# LDP_PWR_v2_0.net
KiCad netlist of a schematic drawn in Altium Designer
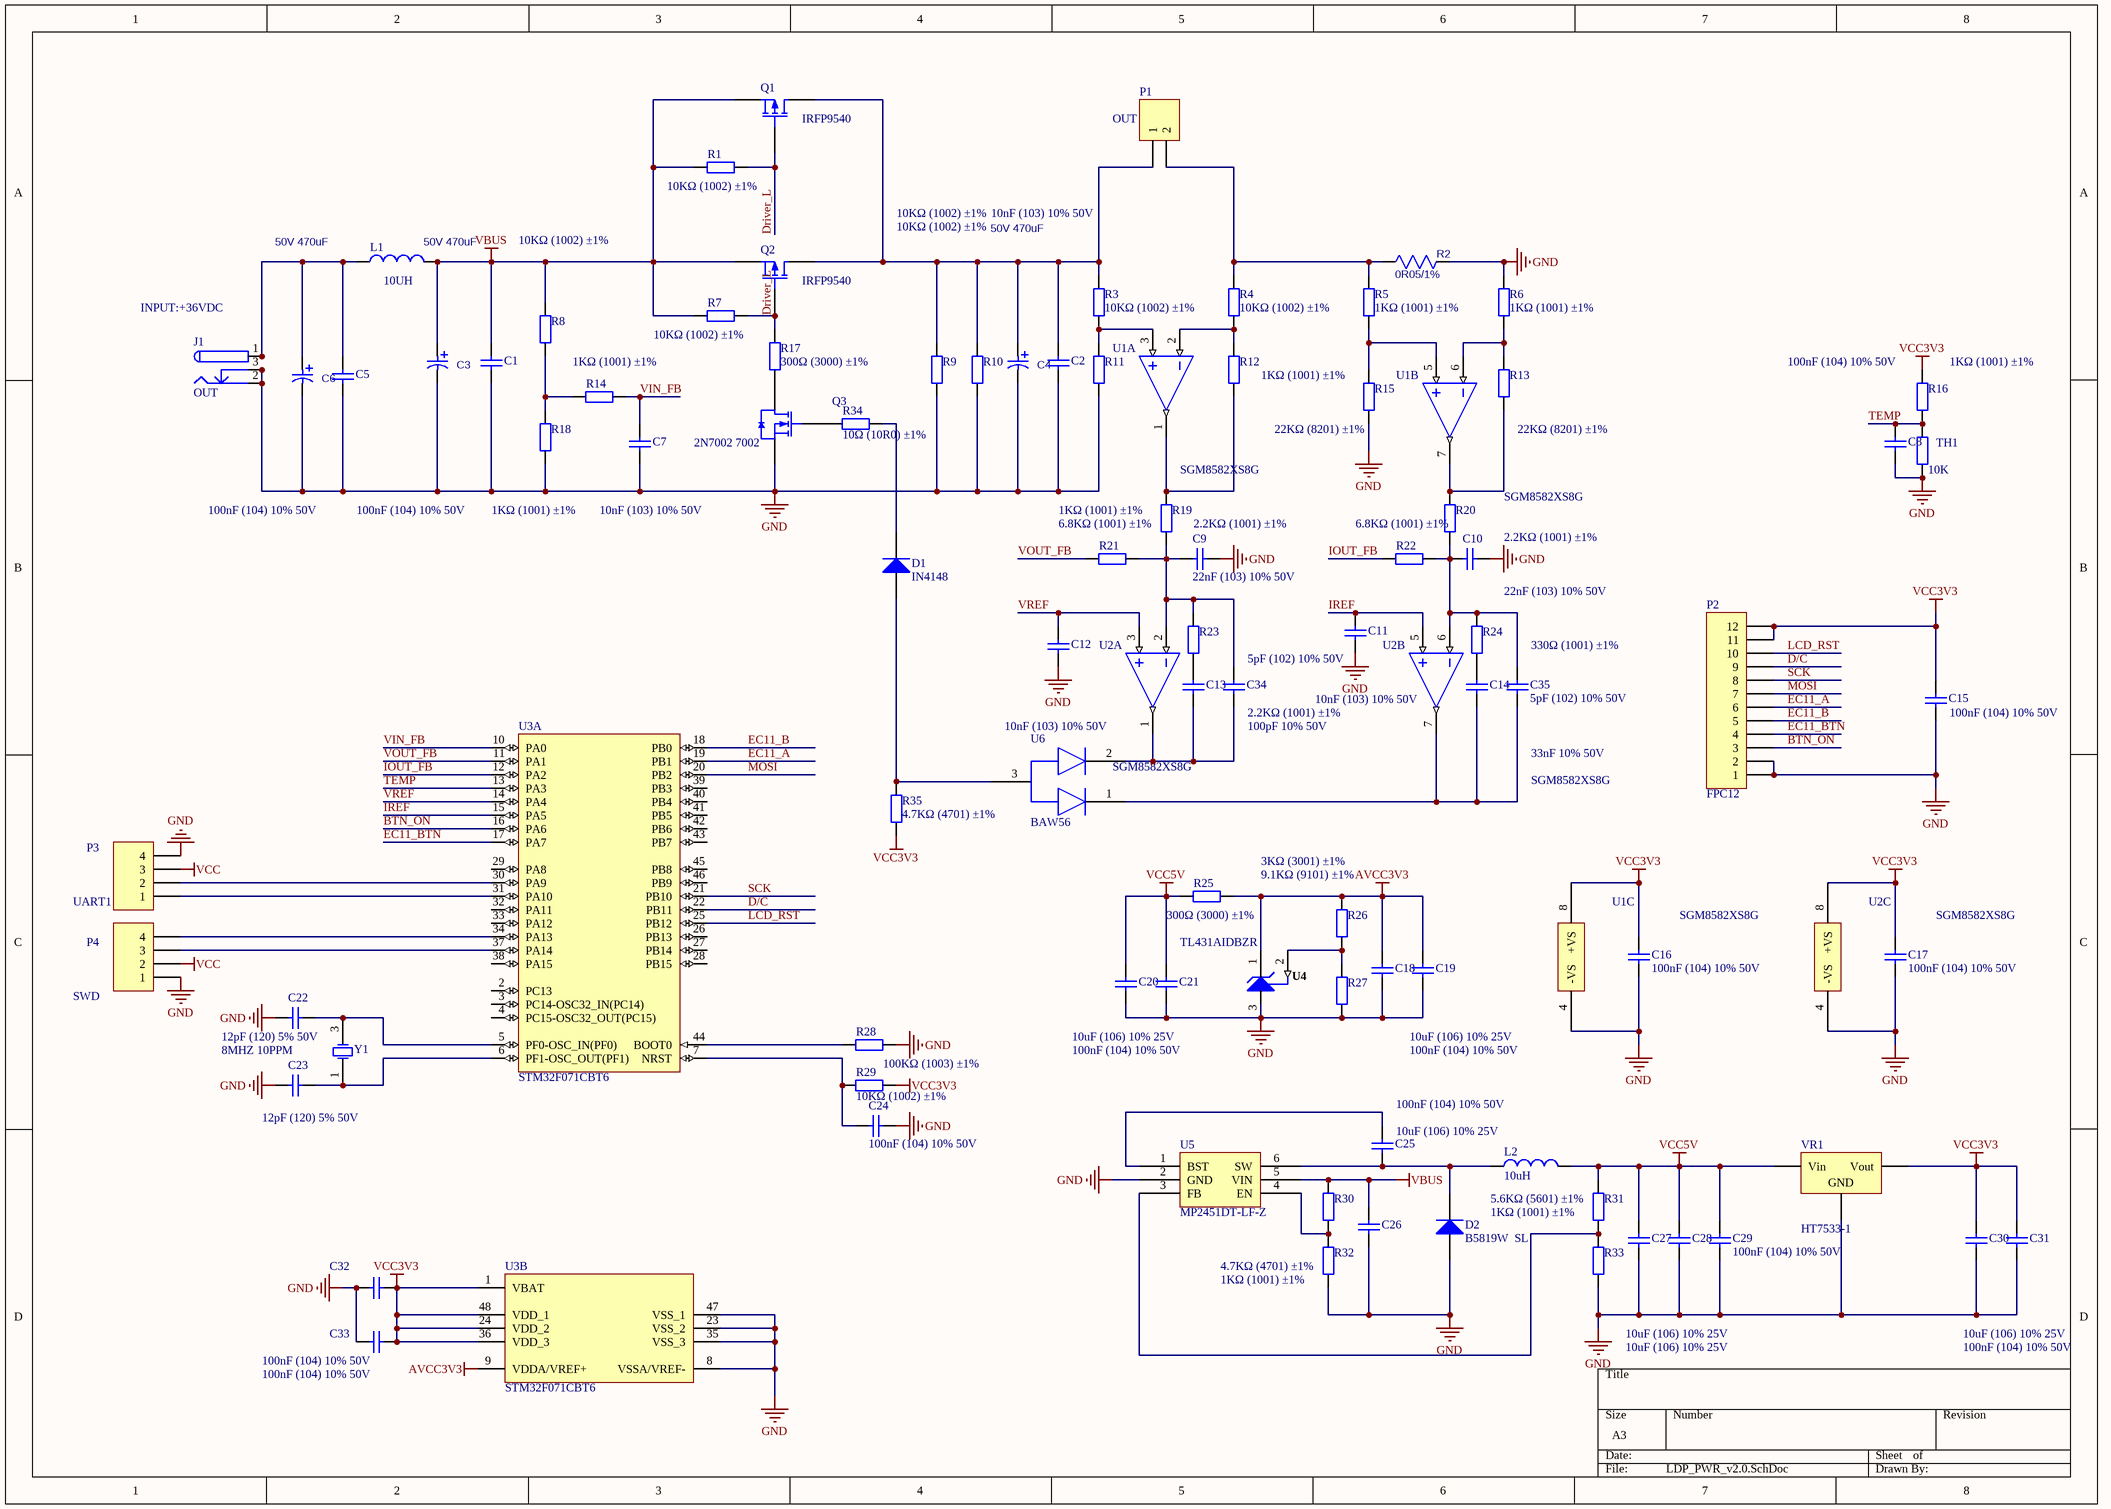
[diagram p0: LDP_PWR_v2.0.SchDoc]

(export (version "E")
  (design (tool "Eeschema 10.0.6"))
  (components
    (comp (ref "C1")
      (value "100nF (104) 10% 50V")
      (footprint "0603_C")
      (description "贴片电容")
      (libsource (lib "Cap") (part "0603 100nF (104) 10% 50V"))
    )
    (comp (ref "C2")
      (value "10nF (103) 10% 50V")
      (footprint "0603_C")
      (description "贴片电容")
      (libsource (lib "Cap") (part "0603 10nF (103) 10% 50V"))
    )
    (comp (ref "C3")
      (value "50V 470uF")
      (footprint "CAP/DIP/10-5")
      (description "Capacitor;400V;20%")
      (fields (field (name "MANUFACTURER") "{Manufacturer}") (field (name "PART NUMBER") "07.0686"))
      (libsource (lib "MPSLab") (part "CAP/ELECT/DIP/OD16.0P7.5"))
    )
    (comp (ref "C4")
      (value "50V 470uF")
      (footprint "CAP/DIP/10-5")
      (description "Capacitor;400V;20%")
      (fields (field (name "MANUFACTURER") "{Manufacturer}") (field (name "PART NUMBER") "07.0686"))
      (libsource (lib "MPSLab") (part "CAP/ELECT/DIP/OD16.0P7.5"))
    )
    (comp (ref "C5")
      (value "100nF (104) 10% 50V")
      (footprint "0603_C")
      (description "贴片电容")
      (libsource (lib "Cap") (part "0603 100nF (104) 10% 50V"))
    )
    (comp (ref "C6")
      (value "50V 470uF")
      (footprint "CAP/DIP/10-5")
      (description "Capacitor;400V;20%")
      (fields (field (name "MANUFACTURER") "{Manufacturer}") (field (name "PART NUMBER") "07.0686"))
      (libsource (lib "MPSLab") (part "CAP/ELECT/DIP/OD16.0P7.5"))
    )
    (comp (ref "C7")
      (value "10nF (103) 10% 50V")
      (footprint "0603_C")
      (description "贴片电容")
      (libsource (lib "Cap") (part "0603 10nF (103) 10% 50V"))
    )
    (comp (ref "C8")
      (value "100nF (104) 10% 50V")
      (footprint "0603_C")
      (description "贴片电容")
      (libsource (lib "Cap") (part "0603 100nF (104) 10% 50V"))
    )
    (comp (ref "C9")
      (value "22nF (103) 10% 50V")
      (footprint "0603_C")
      (description "贴片电容")
      (libsource (lib "Cap") (part "0603 10nF (103) 10% 50V"))
    )
    (comp (ref "C10")
      (value "22nF (103) 10% 50V")
      (footprint "0603_C")
      (description "贴片电容")
      (libsource (lib "Cap") (part "0603 10nF (103) 10% 50V"))
    )
    (comp (ref "C11")
      (value "10nF (103) 10% 50V")
      (footprint "0603_C")
      (description "贴片电容")
      (libsource (lib "Cap") (part "0603 10nF (103) 10% 50V"))
    )
    (comp (ref "C12")
      (value "10nF (103) 10% 50V")
      (footprint "0603_C")
      (description "贴片电容")
      (libsource (lib "Cap") (part "0603 10nF (103) 10% 50V"))
    )
    (comp (ref "C13")
      (value "100pF 10% 50V")
      (footprint "0603_C")
      (description "贴片电容")
      (libsource (lib "Cap") (part "0603 10nF (103) 10% 50V"))
    )
    (comp (ref "C14")
      (value "33nF 10% 50V")
      (footprint "0603_C")
      (description "贴片电容")
      (libsource (lib "Cap") (part "0603 10nF (103) 10% 50V"))
    )
    (comp (ref "C15")
      (value "100nF (104) 10% 50V")
      (footprint "0603_C")
      (description "贴片电容")
      (libsource (lib "Cap") (part "0603 100nF (104) 10% 50V"))
    )
    (comp (ref "C16")
      (value "100nF (104) 10% 50V")
      (footprint "0603_C")
      (description "贴片电容")
      (libsource (lib "Cap") (part "0603 100nF (104) 10% 50V"))
    )
    (comp (ref "C17")
      (value "100nF (104) 10% 50V")
      (footprint "0603_C")
      (description "贴片电容")
      (libsource (lib "Cap") (part "0603 100nF (104) 10% 50V"))
    )
    (comp (ref "C18")
      (value "10uF (106) 10% 25V")
      (footprint "0805_C")
      (description "贴片电容")
      (libsource (lib "Cap") (part "0805 10uF (106) 10% 25V"))
    )
    (comp (ref "C19")
      (value "100nF (104) 10% 50V")
      (footprint "0603_C")
      (description "贴片电容")
      (libsource (lib "Cap") (part "0603 100nF (104) 10% 50V"))
    )
    (comp (ref "C20")
      (value "10uF (106) 10% 25V")
      (footprint "0805_C")
      (description "贴片电容")
      (libsource (lib "Cap") (part "0805 10uF (106) 10% 25V"))
    )
    (comp (ref "C21")
      (value "100nF (104) 10% 50V")
      (footprint "0603_C")
      (description "贴片电容")
      (libsource (lib "Cap") (part "0603 100nF (104) 10% 50V"))
    )
    (comp (ref "C22")
      (value "12pF (120) 5% 50V")
      (footprint "0603_C")
      (description "贴片电容")
      (libsource (lib "Cap") (part "0603 12pF (120) 5% 50V"))
    )
    (comp (ref "C23")
      (value "12pF (120) 5% 50V")
      (footprint "0603_C")
      (description "贴片电容")
      (libsource (lib "Cap") (part "0603 12pF (120) 5% 50V"))
    )
    (comp (ref "C24")
      (value "100nF (104) 10% 50V")
      (footprint "0603_C")
      (description "贴片电容")
      (libsource (lib "Cap") (part "0603 100nF (104) 10% 50V"))
    )
    (comp (ref "C25")
      (value "100nF (104) 10% 50V")
      (footprint "0603_C")
      (description "贴片电容")
      (libsource (lib "Cap") (part "0603 100nF (104) 10% 50V"))
    )
    (comp (ref "C26")
      (value "10uF (106) 10% 25V")
      (footprint "0805_C")
      (description "贴片电容")
      (libsource (lib "Cap") (part "0805 10uF (106) 10% 25V"))
    )
    (comp (ref "C27")
      (value "10uF (106) 10% 25V")
      (footprint "0805_C")
      (description "贴片电容")
      (libsource (lib "Cap") (part "0805 10uF (106) 10% 25V"))
    )
    (comp (ref "C28")
      (value "10uF (106) 10% 25V")
      (footprint "0805_C")
      (description "贴片电容")
      (libsource (lib "Cap") (part "0805 10uF (106) 10% 25V"))
    )
    (comp (ref "C29")
      (value "100nF (104) 10% 50V")
      (footprint "0603_C")
      (description "贴片电容")
      (libsource (lib "Cap") (part "0603 100nF (104) 10% 50V"))
    )
    (comp (ref "C30")
      (value "10uF (106) 10% 25V")
      (footprint "0805_C")
      (description "贴片电容")
      (libsource (lib "Cap") (part "0805 10uF (106) 10% 25V"))
    )
    (comp (ref "C31")
      (value "100nF (104) 10% 50V")
      (footprint "0603_C")
      (description "贴片电容")
      (libsource (lib "Cap") (part "0603 100nF (104) 10% 50V"))
    )
    (comp (ref "C32")
      (value "100nF (104) 10% 50V")
      (footprint "0603_C")
      (description "贴片电容")
      (libsource (lib "Cap") (part "0603 100nF (104) 10% 50V"))
    )
    (comp (ref "C33")
      (value "100nF (104) 10% 50V")
      (footprint "0603_C")
      (description "贴片电容")
      (libsource (lib "Cap") (part "0603 100nF (104) 10% 50V"))
    )
    (comp (ref "C34")
      (value "5pF (102) 10% 50V")
      (footprint "0603_C")
      (description "贴片电容")
      (libsource (lib "Cap") (part "0603 1nF (102) 10% 50V"))
    )
    (comp (ref "C35")
      (value "5pF (102) 10% 50V")
      (footprint "0603_C")
      (description "贴片电容")
      (libsource (lib "Cap") (part "0603 1nF (102) 10% 50V"))
    )
    (comp (ref "D1")
      (value "IN4148")
      (footprint "SOD-123")
      (description "Default Diode")
      (fields (field (name "PUBLISHER") "Altium Limited"))
      (libsource (lib "Miscellaneous Devices") (part "Diode"))
    )
    (comp (ref "D2")
      (value "B5819W  SL")
      (footprint "SOD-123")
      (description "肖特基二极管")
      (libsource (lib "Diode") (part "SOD-123 B5819W  SL"))
    )
    (comp (ref "J1")
      (value "OUT")
      (footprint "CH3.96")
      (description "Low Voltage Power Supply Connector")
      (fields (field (name "PUBLISHER") "Altium Limited"))
      (libsource (lib "Miscellaneous Connectors") (part "PWR2.5"))
    )
    (comp (ref "L1")
      (value "10UH")
      (footprint "L/DIP_6X25")
      (description "Inductor")
      (fields (field (name "PUBLISHER") "Altium Limited"))
      (libsource (lib "Miscellaneous Devices") (part "Inductor"))
    )
    (comp (ref "L2")
      (value "10uH")
      (footprint "CD43 - duplicate")
      (description "Inductor")
      (fields (field (name "PUBLISHER") "Altium Limited"))
      (libsource (lib "Miscellaneous Devices") (part "Inductor"))
    )
    (comp (ref "P1")
      (value "OUT")
      (footprint "CH3.96")
      (description "Header, 2-Pin")
      (fields (field (name "PUBLISHER") "Altium Limited"))
      (libsource (lib "Miscellaneous Connectors") (part "Header 2"))
    )
    (comp (ref "P2")
      (value "FPC12")
      (footprint "FPC_12")
      (description "Header, 12-Pin")
      (fields (field (name "PUBLISHER") "Altium Limited"))
      (libsource (lib "Miscellaneous Connectors") (part "Header 12"))
    )
    (comp (ref "P3")
      (value "UART1")
      (footprint "HDR1X4")
      (description "Header, 4-Pin")
      (fields (field (name "PUBLISHER") "Altium Limited"))
      (libsource (lib "Miscellaneous Connectors") (part "Header 4"))
    )
    (comp (ref "P4")
      (value "SWD")
      (footprint "HDR1X4")
      (description "Header, 4-Pin")
      (fields (field (name "PUBLISHER") "Altium Limited"))
      (libsource (lib "Miscellaneous Connectors") (part "Header 4"))
    )
    (comp (ref "Q1")
      (value "IRFP9540")
      (footprint "TO-220(TO-220-3)")
      (description "P-Channel MOSFET")
      (fields (field (name "PUBLISHER") "Altium Limited"))
      (libsource (lib "Miscellaneous Devices") (part "MOSFET-P"))
    )
    (comp (ref "Q2")
      (value "IRFP9540")
      (footprint "TO-220(TO-220-3)")
      (description "P-Channel MOSFET")
      (fields (field (name "PUBLISHER") "Altium Limited"))
      (libsource (lib "Miscellaneous Devices") (part "MOSFET-P"))
    )
    (comp (ref "Q3")
      (value "2N7002 7002")
      (footprint "SOT-23(SOT-23-3)")
      (description "MOS(场效应管)")
      (libsource (lib "MOS") (part "2N7002 7002"))
    )
    (comp (ref "R1")
      (value "10KΩ (1002) ±1%")
      (footprint "1206_R")
      (description "贴片电阻")
      (libsource (lib "") (part "1206 10KΩ (1002) 1%_1"))
    )
    (comp (ref "R2")
      (value "0R05/1%")
      (footprint "2512_R")
      (description "Film Resistor;5%;")
      (fields (field (name "MANUFACTURER") "Yageo") (field (name "PART NUMBER") "06.0281"))
      (libsource (lib "MPSLab") (part "RES/0603"))
    )
    (comp (ref "R3")
      (value "10KΩ (1002) ±1%")
      (footprint "0603_R")
      (description "贴片电阻")
      (libsource (lib "") (part "0603 10KΩ (1002) 1%_1"))
    )
    (comp (ref "R4")
      (value "10KΩ (1002) ±1%")
      (footprint "0603_R")
      (description "贴片电阻")
      (libsource (lib "") (part "0603 10KΩ (1002) 1%_1"))
    )
    (comp (ref "R5")
      (value "1KΩ (1001) ±1%")
      (footprint "0603_R")
      (description "贴片电阻")
      (libsource (lib "") (part "0603 1KΩ (1001) 1%_1"))
    )
    (comp (ref "R6")
      (value "1KΩ (1001) ±1%")
      (footprint "0603_R")
      (description "贴片电阻")
      (libsource (lib "") (part "0603 1KΩ (1001) 1%_1"))
    )
    (comp (ref "R7")
      (value "10KΩ (1002) ±1%")
      (footprint "1206_R")
      (description "贴片电阻")
      (libsource (lib "") (part "1206 10KΩ (1002) 1%_1"))
    )
    (comp (ref "R8")
      (value "10KΩ (1002) ±1%")
      (footprint "0603_R")
      (description "贴片电阻")
      (libsource (lib "") (part "0603 10KΩ (1002) 1%_1"))
    )
    (comp (ref "R9")
      (value "10KΩ (1002) ±1%")
      (footprint "1206_R")
      (description "贴片电阻")
      (libsource (lib "RES") (part "1206 10KΩ (1002) 1%"))
    )
    (comp (ref "R10")
      (value "10KΩ (1002) ±1%")
      (footprint "1206_R")
      (description "贴片电阻")
      (libsource (lib "RES") (part "1206 10KΩ (1002) 1%"))
    )
    (comp (ref "R11")
      (value "1KΩ (1001) ±1%")
      (footprint "0603_R")
      (description "贴片电阻")
      (libsource (lib "") (part "0603 1KΩ (1001) 1%_1"))
    )
    (comp (ref "R12")
      (value "1KΩ (1001) ±1%")
      (footprint "0603_R")
      (description "贴片电阻")
      (libsource (lib "") (part "0603 1KΩ (1001) 1%_1"))
    )
    (comp (ref "R13")
      (value "22KΩ (8201) ±1%")
      (footprint "0603_R")
      (description "贴片电阻")
      (libsource (lib "RES") (part "0603 8.2KΩ (8201) 1%"))
    )
    (comp (ref "R14")
      (value "1KΩ (1001) ±1%")
      (footprint "0603_R")
      (description "贴片电阻")
      (libsource (lib "RES") (part "0603 1KΩ (1001) 1%"))
    )
    (comp (ref "R15")
      (value "22KΩ (8201) ±1%")
      (footprint "0603_R")
      (description "贴片电阻")
      (libsource (lib "RES") (part "0603 8.2KΩ (8201) 1%"))
    )
    (comp (ref "R16")
      (value "1KΩ (1001) ±1%")
      (footprint "0603_R")
      (description "贴片电阻")
      (libsource (lib "") (part "0603 1KΩ (1001) 1%_1"))
    )
    (comp (ref "R17")
      (value "300Ω (3000) ±1%")
      (footprint "1206_R")
      (description "贴片电阻")
      (libsource (lib "RES") (part "1206 300Ω (3000) 1%"))
    )
    (comp (ref "R18")
      (value "1KΩ (1001) ±1%")
      (footprint "0603_R")
      (description "贴片电阻")
      (libsource (lib "") (part "0603 1KΩ (1001) 1%_1"))
    )
    (comp (ref "R19")
      (value "2.2KΩ (1001) ±1%")
      (footprint "0603_R")
      (description "贴片电阻")
      (libsource (lib "") (part "0603 1KΩ (1001) 1%_1"))
    )
    (comp (ref "R20")
      (value "2.2KΩ (1001) ±1%")
      (footprint "0603_R")
      (description "贴片电阻")
      (libsource (lib "") (part "0603 1KΩ (1001) 1%_1"))
    )
    (comp (ref "R21")
      (value "6.8KΩ (1001) ±1%")
      (footprint "0603_R")
      (description "贴片电阻")
      (libsource (lib "RES") (part "0603 1KΩ (1001) 1%"))
    )
    (comp (ref "R22")
      (value "6.8KΩ (1001) ±1%")
      (footprint "0603_R")
      (description "贴片电阻")
      (libsource (lib "RES") (part "0603 1KΩ (1001) 1%"))
    )
    (comp (ref "R23")
      (value "2.2KΩ (1001) ±1%")
      (footprint "0603_R")
      (description "贴片电阻")
      (libsource (lib "") (part "0603 1KΩ (1001) 1%_2"))
    )
    (comp (ref "R24")
      (value "330Ω (1001) ±1%")
      (footprint "0603_R")
      (description "贴片电阻")
      (libsource (lib "") (part "0603 1KΩ (1001) 1%_2"))
    )
    (comp (ref "R25")
      (value "300Ω (3000) ±1%")
      (footprint "1206_R")
      (description "贴片电阻")
      (libsource (lib "") (part "1206 300Ω (3000) 1%_1"))
    )
    (comp (ref "R26")
      (value "3KΩ (3001) ±1%")
      (footprint "0603_R")
      (description "贴片电阻")
      (libsource (lib "RES") (part "0603 3KΩ (3001) 1%"))
    )
    (comp (ref "R27")
      (value "9.1KΩ (9101) ±1%")
      (footprint "0603_R")
      (description "贴片电阻")
      (libsource (lib "RES") (part "0603 9.1KΩ (9101) 1%"))
    )
    (comp (ref "R28")
      (value "100KΩ (1003) ±1%")
      (footprint "0603_R")
      (description "贴片电阻")
      (libsource (lib "RES") (part "0603 100KΩ (1003) 1%"))
    )
    (comp (ref "R29")
      (value "10KΩ (1002) ±1%")
      (footprint "0603_R")
      (description "贴片电阻")
      (libsource (lib "RES") (part "0603 10KΩ (1002) 1%"))
    )
    (comp (ref "R30")
      (value "4.7KΩ (4701) ±1%")
      (footprint "0603_R")
      (description "贴片电阻")
      (libsource (lib "RES") (part "0603 4.7KΩ (4701) 1%"))
    )
    (comp (ref "R31")
      (value "5.6KΩ (5601) ±1%")
      (footprint "0603_R")
      (description "贴片电阻")
      (libsource (lib "RES") (part "0603 5.6KΩ (5601) 1%"))
    )
    (comp (ref "R32")
      (value "1KΩ (1001) ±1%")
      (footprint "0603_R")
      (description "贴片电阻")
      (libsource (lib "") (part "0603 1KΩ (1001) 1%_1"))
    )
    (comp (ref "R33")
      (value "1KΩ (1001) ±1%")
      (footprint "0603_R")
      (description "贴片电阻")
      (libsource (lib "") (part "0603 1KΩ (1001) 1%_1"))
    )
    (comp (ref "R34")
      (value "10Ω (10R0) ±1%")
      (footprint "0603_R")
      (description "贴片电阻")
      (libsource (lib "RES") (part "0603 10Ω (10R0) 1%"))
    )
    (comp (ref "R35")
      (value "4.7KΩ (4701) ±1%")
      (footprint "0603_R")
      (description "贴片电阻")
      (libsource (lib "RES") (part "0603 4.7KΩ (4701) 1%"))
    )
    (comp (ref "TH1")
      (value "10K")
      (footprint "NTC_2.5MM")
      (description "Resistor")
      (fields (field (name "Comment") "NTC 10K") (field (name "PUBLISHER") "Altium Limited"))
      (libsource (lib "Miscellaneous Devices") (part "Res2"))
    )
    (comp (ref "U1")
      (value "SGM8582XS8G")
      (footprint "SOIC-8_208mil")
      (description "运放")
      (libsource (lib "") (part "SGM8292XS8G_1"))
    )
    (comp (ref "U2")
      (value "SGM8582XS8G")
      (footprint "SOIC-8_208mil")
      (description "运放")
      (libsource (lib "") (part "SGM8292XS8G_1"))
    )
    (comp (ref "U3")
      (value "STM32F071CBT6")
      (footprint "STM-LQFP48_N")
      (fields (field (name "PARTNUMBER") "STM32F303CCT6"))
      (libsource (lib "STMicroelectronics STM32 F3") (part "STM32F303CCT6"))
    )
    (comp (ref "U4")
      (value "TL431AIDBZR")
      (footprint "TI-DBZ3_N")
      (fields (field (name "MANUFACTURER") "Texas Instruments"))
      (libsource (lib "TI Power Management Shunt Voltage Reference") (part "TL431AIDBZR"))
    )
    (comp (ref "U5")
      (value "MP2451DT-LF-Z")
      (footprint "SOT-23-6")
      (description "DC-DC芯片")
      (libsource (lib "IC") (part "MP2451DT-LF-Z_[C14123]"))
    )
    (comp (ref "U6") (value "BAW56") (footprint "SOT-23(SOT-23-3)") (libsource (lib "Diode") (part "BAW56")))
    (comp (ref "VR1")
      (value "HT7533-1")
      (footprint "SOT-89(SOT-89-3)")
      (description "低压差线性稳压(LDO)")
      (libsource (lib "LDO") (part "SOT-89 HT7533-1"))
    )
    (comp (ref "Y1")
      (value "8MHZ 10PPM")
      (footprint "SMD-3225_4P")
      (description "贴片晶振")
      (libsource (lib "CrystalOscillator") (part "SMD-3225_4P  12MHZ 20PF 10PPM"))
    )
  )
  (nets
    (net (code "1") (name "/BTN_ON") (class "Default")
      (node (ref "P2") (pin "3") (pinfunction "3_3") (pintype "passive"))
      (node (ref "U3") (pin "16") (pinfunction "PA6_16") (pintype "bidirectional"))
    )
    (net (code "2") (name "/Driver_L") (class "Default")
      (node (ref "Q1") (pin "2") (pinfunction "G_2") (pintype "passive"))
      (node (ref "Q2") (pin "2") (pinfunction "G_2") (pintype "passive"))
      (node (ref "R1") (pin "2") (pinfunction "2_2") (pintype "passive"))
      (node (ref "R17") (pin "2") (pinfunction "2_2") (pintype "passive"))
      (node (ref "R7") (pin "2") (pinfunction "2_2") (pintype "passive"))
    )
    (net (code "3") (name "/D{slash}C") (class "Default")
      (node (ref "P2") (pin "9") (pinfunction "9_9") (pintype "passive"))
      (node (ref "U3") (pin "22") (pinfunction "PB11_22") (pintype "bidirectional"))
    )
    (net (code "4") (name "/EC11_A") (class "Default")
      (node (ref "P2") (pin "6") (pinfunction "6_6") (pintype "passive"))
      (node (ref "U3") (pin "19") (pinfunction "PB1_19") (pintype "bidirectional"))
    )
    (net (code "5") (name "/EC11_B") (class "Default")
      (node (ref "P2") (pin "5") (pinfunction "5_5") (pintype "passive"))
      (node (ref "U3") (pin "18") (pinfunction "PB0_18") (pintype "bidirectional"))
    )
    (net (code "6") (name "/EC11_BTN") (class "Default")
      (node (ref "P2") (pin "4") (pinfunction "4_4") (pintype "passive"))
      (node (ref "U3") (pin "17") (pinfunction "PA7_17") (pintype "bidirectional"))
    )
    (net (code "7") (name "/IOUT_FB") (class "Default")
      (node (ref "R22") (pin "2") (pinfunction "2_2") (pintype "passive"))
      (node (ref "U3") (pin "12") (pinfunction "PA2_12") (pintype "bidirectional"))
    )
    (net (code "8") (name "/IREF") (class "Default")
      (node (ref "C11") (pin "1") (pinfunction "1_1") (pintype "passive"))
      (node (ref "U2") (pin "5") (pinfunction "IN+_5") (pintype "input"))
      (node (ref "U3") (pin "15") (pinfunction "PA5_15") (pintype "bidirectional"))
    )
    (net (code "9") (name "/LCD_RST") (class "Default")
      (node (ref "P2") (pin "10") (pinfunction "10_10") (pintype "passive"))
      (node (ref "U3") (pin "25") (pinfunction "PB12_25") (pintype "bidirectional"))
    )
    (net (code "10") (name "/MOSI") (class "Default")
      (node (ref "P2") (pin "7") (pinfunction "7_7") (pintype "passive"))
      (node (ref "U3") (pin "20") (pinfunction "PB2_20") (pintype "bidirectional"))
    )
    (net (code "11") (name "/SCK") (class "Default")
      (node (ref "P2") (pin "8") (pinfunction "8_8") (pintype "passive"))
      (node (ref "U3") (pin "21") (pinfunction "PB10_21") (pintype "bidirectional"))
    )
    (net (code "12") (name "/TEMP") (class "Default")
      (node (ref "C8") (pin "2") (pinfunction "2_2") (pintype "passive"))
      (node (ref "R16") (pin "1") (pinfunction "1_1") (pintype "passive"))
      (node (ref "TH1") (pin "2") (pinfunction "2_2") (pintype "passive"))
      (node (ref "U3") (pin "13") (pinfunction "PA3_13") (pintype "bidirectional"))
    )
    (net (code "13") (name "/VIN_FB") (class "Default")
      (node (ref "C7") (pin "2") (pinfunction "2_2") (pintype "passive"))
      (node (ref "R14") (pin "1") (pinfunction "1_1") (pintype "passive"))
      (node (ref "U3") (pin "10") (pinfunction "PA0_10") (pintype "bidirectional"))
    )
    (net (code "14") (name "/VOUT_FB") (class "Default")
      (node (ref "R21") (pin "2") (pinfunction "2_2") (pintype "passive"))
      (node (ref "U3") (pin "11") (pinfunction "PA1_11") (pintype "bidirectional"))
    )
    (net (code "15") (name "/VREF") (class "Default")
      (node (ref "C12") (pin "1") (pinfunction "1_1") (pintype "passive"))
      (node (ref "U2") (pin "3") (pinfunction "IN+_3") (pintype "input"))
      (node (ref "U3") (pin "14") (pinfunction "PA4_14") (pintype "bidirectional"))
    )
    (net (code "16") (name "AVCC3V3") (class "Default")
      (node (ref "C18") (pin "2") (pinfunction "2_2") (pintype "passive"))
      (node (ref "C19") (pin "2") (pinfunction "2_2") (pintype "passive"))
      (node (ref "R25") (pin "2") (pinfunction "2_2") (pintype "passive"))
      (node (ref "R26") (pin "2") (pinfunction "2_2") (pintype "passive"))
      (node (ref "U3") (pin "9") (pinfunction "VDDA/VREF+_9") (pintype "power_in"))
      (node (ref "U4") (pin "1") (pinfunction "CATHODE_1") (pintype "passive"))
    )
    (net (code "17") (name "GND") (class "Default")
      (node (ref "C1") (pin "1") (pinfunction "1_1") (pintype "passive"))
      (node (ref "C10") (pin "1") (pinfunction "1_1") (pintype "passive"))
      (node (ref "C11") (pin "2") (pinfunction "2_2") (pintype "passive"))
      (node (ref "C12") (pin "2") (pinfunction "2_2") (pintype "passive"))
      (node (ref "C15") (pin "1") (pinfunction "1_1") (pintype "passive"))
      (node (ref "C16") (pin "1") (pinfunction "1_1") (pintype "passive"))
      (node (ref "C17") (pin "1") (pinfunction "1_1") (pintype "passive"))
      (node (ref "C18") (pin "1") (pinfunction "1_1") (pintype "passive"))
      (node (ref "C19") (pin "1") (pinfunction "1_1") (pintype "passive"))
      (node (ref "C2") (pin "2") (pinfunction "2_2") (pintype "passive"))
      (node (ref "C20") (pin "1") (pinfunction "1_1") (pintype "passive"))
      (node (ref "C21") (pin "1") (pinfunction "1_1") (pintype "passive"))
      (node (ref "C22") (pin "1") (pinfunction "1_1") (pintype "passive"))
      (node (ref "C23") (pin "1") (pinfunction "1_1") (pintype "passive"))
      (node (ref "C24") (pin "2") (pinfunction "2_2") (pintype "passive"))
      (node (ref "C26") (pin "1") (pinfunction "1_1") (pintype "passive"))
      (node (ref "C27") (pin "1") (pinfunction "1_1") (pintype "passive"))
      (node (ref "C28") (pin "1") (pinfunction "1_1") (pintype "passive"))
      (node (ref "C29") (pin "1") (pinfunction "1_1") (pintype "passive"))
      (node (ref "C3") (pin "2") (pintype "passive"))
      (node (ref "C30") (pin "1") (pinfunction "1_1") (pintype "passive"))
      (node (ref "C31") (pin "1") (pinfunction "1_1") (pintype "passive"))
      (node (ref "C32") (pin "2") (pinfunction "2_2") (pintype "passive"))
      (node (ref "C33") (pin "2") (pinfunction "2_2") (pintype "passive"))
      (node (ref "C4") (pin "2") (pintype "passive"))
      (node (ref "C5") (pin "1") (pinfunction "1_1") (pintype "passive"))
      (node (ref "C6") (pin "2") (pintype "passive"))
      (node (ref "C7") (pin "1") (pinfunction "1_1") (pintype "passive"))
      (node (ref "C8") (pin "1") (pinfunction "1_1") (pintype "passive"))
      (node (ref "C9") (pin "1") (pinfunction "1_1") (pintype "passive"))
      (node (ref "D2") (pin "1") (pinfunction "A_1") (pintype "passive"))
      (node (ref "J1") (pin "2") (pinfunction "2_2") (pintype "power_in"))
      (node (ref "J1") (pin "2A") (pinfunction "2A_2A") (pintype "power_in"))
      (node (ref "J1") (pin "2B") (pinfunction "2B_2B") (pintype "power_in"))
      (node (ref "J1") (pin "3") (pinfunction "3_3") (pintype "power_in"))
      (node (ref "J1") (pin "3A") (pinfunction "3A_3A") (pintype "power_in"))
      (node (ref "J1") (pin "3B") (pinfunction "3B_3B") (pintype "power_in"))
      (node (ref "P2") (pin "1") (pinfunction "1_1") (pintype "passive"))
      (node (ref "P2") (pin "2") (pinfunction "2_2") (pintype "passive"))
      (node (ref "P3") (pin "4") (pinfunction "4_4") (pintype "passive"))
      (node (ref "P4") (pin "1") (pinfunction "1_1") (pintype "passive"))
      (node (ref "Q3") (pin "2") (pinfunction "S_2") (pintype "passive"))
      (node (ref "R10") (pin "1") (pinfunction "1_1") (pintype "passive"))
      (node (ref "R11") (pin "1") (pinfunction "1_1") (pintype "passive"))
      (node (ref "R15") (pin "1") (pinfunction "1_1") (pintype "passive"))
      (node (ref "R18") (pin "1") (pinfunction "1_1") (pintype "passive"))
      (node (ref "R2") (pin "1") (pintype "passive"))
      (node (ref "R27") (pin "1") (pinfunction "1_1") (pintype "passive"))
      (node (ref "R28") (pin "2") (pinfunction "2_2") (pintype "passive"))
      (node (ref "R32") (pin "1") (pinfunction "1_1") (pintype "passive"))
      (node (ref "R33") (pin "1") (pinfunction "1_1") (pintype "passive"))
      (node (ref "R6") (pin "2") (pinfunction "2_2") (pintype "passive"))
      (node (ref "R9") (pin "1") (pinfunction "1_1") (pintype "passive"))
      (node (ref "TH1") (pin "1") (pinfunction "1_1") (pintype "passive"))
      (node (ref "U1") (pin "4") (pinfunction "-VS_4") (pintype "passive"))
      (node (ref "U2") (pin "4") (pinfunction "-VS_4") (pintype "passive"))
      (node (ref "U3") (pin "23") (pinfunction "VSS_2_23") (pintype "power_in"))
      (node (ref "U3") (pin "35") (pinfunction "VSS_3_35") (pintype "power_in"))
      (node (ref "U3") (pin "47") (pinfunction "VSS_1_47") (pintype "power_in"))
      (node (ref "U3") (pin "8") (pinfunction "VSSA/VREF-_8") (pintype "power_in"))
      (node (ref "U4") (pin "3") (pinfunction "ANODE_3") (pintype "passive"))
      (node (ref "U5") (pin "2") (pinfunction "GND_2") (pintype "passive"))
      (node (ref "VR1") (pin "1") (pinfunction "GND_1") (pintype "passive"))
    )
    (net (code "18") (name "Net-(C5-Pad2)") (class "Default")
      (node (ref "C5") (pin "2") (pinfunction "2_2") (pintype "passive"))
      (node (ref "C6") (pin "1") (pintype "passive"))
      (node (ref "J1") (pin "1") (pinfunction "1_1") (pintype "power_in"))
      (node (ref "J1") (pin "1B") (pinfunction "1B_1B") (pintype "power_in"))
      (node (ref "J1") (pin "2") (pinfunction "2_2") (pintype "power_in"))
      (node (ref "L1") (pin "1") (pinfunction "1_1") (pintype "passive"))
    )
    (net (code "19") (name "Net-(C13-Pad1)") (class "Default")
      (node (ref "C13") (pin "1") (pinfunction "1_1") (pintype "passive"))
      (node (ref "R23") (pin "2") (pinfunction "2_2") (pintype "passive"))
    )
    (net (code "20") (name "Net-(C14-Pad1)") (class "Default")
      (node (ref "C14") (pin "1") (pinfunction "1_1") (pintype "passive"))
      (node (ref "R24") (pin "2") (pinfunction "2_2") (pintype "passive"))
    )
    (net (code "21") (name "Net-(D1-A)") (class "Default")
      (node (ref "D1") (pin "1") (pinfunction "A_1") (pintype "passive"))
      (node (ref "R35") (pin "2") (pinfunction "2_2") (pintype "passive"))
      (node (ref "U6") (pin "3") (pinfunction "3_3") (pintype "passive"))
    )
    (net (code "22") (name "Net-(D1-K)") (class "Default")
      (node (ref "D1") (pin "2") (pinfunction "K_2") (pintype "passive"))
      (node (ref "R34") (pin "2") (pinfunction "2_2") (pintype "passive"))
    )
    (net (code "23") (name "Net-(D2-K)") (class "Default")
      (node (ref "C25") (pin "1") (pinfunction "1_1") (pintype "passive"))
      (node (ref "D2") (pin "2") (pinfunction "K_2") (pintype "passive"))
      (node (ref "L2") (pin "1") (pinfunction "1_1") (pintype "passive"))
      (node (ref "U5") (pin "6") (pinfunction "SW_6") (pintype "passive"))
    )
    (net (code "24") (name "Net-(P1-Pad2)") (class "Default")
      (node (ref "P1") (pin "2") (pinfunction "2_2") (pintype "passive"))
      (node (ref "R2") (pin "2") (pintype "passive"))
      (node (ref "R4") (pin "2") (pinfunction "2_2") (pintype "passive"))
      (node (ref "R5") (pin "2") (pinfunction "2_2") (pintype "passive"))
    )
    (net (code "25") (name "Net-(Q1-D)") (class "Default")
      (node (ref "C2") (pin "1") (pinfunction "1_1") (pintype "passive"))
      (node (ref "C4") (pin "1") (pintype "passive"))
      (node (ref "P1") (pin "1") (pinfunction "1_1") (pintype "passive"))
      (node (ref "Q1") (pin "1") (pinfunction "D_1") (pintype "passive"))
      (node (ref "Q2") (pin "1") (pinfunction "D_1") (pintype "passive"))
      (node (ref "R10") (pin "2") (pinfunction "2_2") (pintype "passive"))
      (node (ref "R3") (pin "2") (pinfunction "2_2") (pintype "passive"))
      (node (ref "R9") (pin "2") (pinfunction "2_2") (pintype "passive"))
    )
    (net (code "26") (name "Net-(Q3-D)") (class "Default")
      (node (ref "Q3") (pin "3") (pinfunction "D_3") (pintype "passive"))
      (node (ref "R17") (pin "1") (pinfunction "1_1") (pintype "passive"))
    )
    (net (code "27") (name "Net-(Q3-G)") (class "Default")
      (node (ref "Q3") (pin "1") (pinfunction "G_1") (pintype "passive"))
      (node (ref "R34") (pin "1") (pinfunction "1_1") (pintype "passive"))
    )
    (net (code "28") (name "Net-(R14-Pad2)") (class "Default")
      (node (ref "R14") (pin "2") (pinfunction "2_2") (pintype "passive"))
      (node (ref "R18") (pin "2") (pinfunction "2_2") (pintype "passive"))
      (node (ref "R8") (pin "1") (pinfunction "1_1") (pintype "passive"))
    )
    (net (code "29") (name "Net-(U1A-IN+)") (class "Default")
      (node (ref "R11") (pin "2") (pinfunction "2_2") (pintype "passive"))
      (node (ref "R3") (pin "1") (pinfunction "1_1") (pintype "passive"))
      (node (ref "U1") (pin "3") (pinfunction "IN+_3") (pintype "input"))
    )
    (net (code "30") (name "Net-(U1A-IN-)") (class "Default")
      (node (ref "R12") (pin "2") (pinfunction "2_2") (pintype "passive"))
      (node (ref "R4") (pin "1") (pinfunction "1_1") (pintype "passive"))
      (node (ref "U1") (pin "2") (pinfunction "IN-_2") (pintype "input"))
    )
    (net (code "31") (name "Net-(U1A-OUT)") (class "Default")
      (node (ref "R12") (pin "1") (pinfunction "1_1") (pintype "passive"))
      (node (ref "R19") (pin "2") (pinfunction "2_2") (pintype "passive"))
      (node (ref "U1") (pin "1") (pinfunction "OUT_1") (pintype "output"))
    )
    (net (code "32") (name "Net-(U1B-IN+)") (class "Default")
      (node (ref "R15") (pin "2") (pinfunction "2_2") (pintype "passive"))
      (node (ref "R5") (pin "1") (pinfunction "1_1") (pintype "passive"))
      (node (ref "U1") (pin "5") (pinfunction "IN+_5") (pintype "input"))
    )
    (net (code "33") (name "Net-(U1B-IN-)") (class "Default")
      (node (ref "R13") (pin "2") (pinfunction "2_2") (pintype "passive"))
      (node (ref "R6") (pin "1") (pinfunction "1_1") (pintype "passive"))
      (node (ref "U1") (pin "6") (pinfunction "IN-_6") (pintype "input"))
    )
    (net (code "34") (name "Net-(U1B-OUT)") (class "Default")
      (node (ref "R13") (pin "1") (pinfunction "1_1") (pintype "passive"))
      (node (ref "R20") (pin "2") (pinfunction "2_2") (pintype "passive"))
      (node (ref "U1") (pin "7") (pinfunction "OUT_7") (pintype "output"))
    )
    (net (code "35") (name "Net-(U2A-IN-)") (class "Default")
      (node (ref "C34") (pin "2") (pinfunction "2_2") (pintype "passive"))
      (node (ref "C9") (pin "2") (pinfunction "2_2") (pintype "passive"))
      (node (ref "R19") (pin "1") (pinfunction "1_1") (pintype "passive"))
      (node (ref "R21") (pin "1") (pinfunction "1_1") (pintype "passive"))
      (node (ref "R23") (pin "1") (pinfunction "1_1") (pintype "passive"))
      (node (ref "U2") (pin "2") (pinfunction "IN-_2") (pintype "input"))
    )
    (net (code "36") (name "Net-(U2A-OUT)") (class "Default")
      (node (ref "C13") (pin "2") (pinfunction "2_2") (pintype "passive"))
      (node (ref "C34") (pin "1") (pinfunction "1_1") (pintype "passive"))
      (node (ref "U2") (pin "1") (pinfunction "OUT_1") (pintype "output"))
    )
    (net (code "37") (name "Net-(U2B-IN-)") (class "Default")
      (node (ref "C10") (pin "2") (pinfunction "2_2") (pintype "passive"))
      (node (ref "C35") (pin "2") (pinfunction "2_2") (pintype "passive"))
      (node (ref "R20") (pin "1") (pinfunction "1_1") (pintype "passive"))
      (node (ref "R22") (pin "1") (pinfunction "1_1") (pintype "passive"))
      (node (ref "R24") (pin "1") (pinfunction "1_1") (pintype "passive"))
      (node (ref "U2") (pin "6") (pinfunction "IN-_6") (pintype "input"))
    )
    (net (code "38") (name "Net-(U2B-OUT)") (class "Default")
      (node (ref "C14") (pin "2") (pinfunction "2_2") (pintype "passive"))
      (node (ref "C35") (pin "1") (pinfunction "1_1") (pintype "passive"))
      (node (ref "U2") (pin "7") (pinfunction "OUT_7") (pintype "output"))
    )
    (net (code "39") (name "Net-(U3A-BOOT0)") (class "Default")
      (node (ref "R28") (pin "1") (pinfunction "1_1") (pintype "passive"))
      (node (ref "U3") (pin "44") (pinfunction "BOOT0_44") (pintype "input"))
    )
    (net (code "40") (name "Net-(U3A-NRST)") (class "Default")
      (node (ref "C24") (pin "1") (pinfunction "1_1") (pintype "passive"))
      (node (ref "R29") (pin "1") (pinfunction "1_1") (pintype "passive"))
      (node (ref "U3") (pin "7") (pinfunction "NRST_7") (pintype "bidirectional"))
    )
    (net (code "41") (name "Net-(U3A-PA9)") (class "Default")
      (node (ref "P3") (pin "2") (pinfunction "2_2") (pintype "passive"))
      (node (ref "U3") (pin "30") (pinfunction "PA9_30") (pintype "bidirectional"))
    )
    (net (code "42") (name "Net-(U3A-PA10)") (class "Default")
      (node (ref "P3") (pin "1") (pinfunction "1_1") (pintype "passive"))
      (node (ref "U3") (pin "31") (pinfunction "PA10_31") (pintype "bidirectional"))
    )
    (net (code "43") (name "Net-(U3A-PA13)") (class "Default")
      (node (ref "P4") (pin "4") (pinfunction "4_4") (pintype "passive"))
      (node (ref "U3") (pin "34") (pinfunction "PA13_34") (pintype "bidirectional"))
    )
    (net (code "44") (name "Net-(U3A-PA14)") (class "Default")
      (node (ref "P4") (pin "3") (pinfunction "3_3") (pintype "passive"))
      (node (ref "U3") (pin "37") (pinfunction "PA14_37") (pintype "bidirectional"))
    )
    (net (code "45") (name "Net-(U3A-PF0-OSC_IN(PF0))") (class "Default")
      (node (ref "C22") (pin "2") (pinfunction "2_2") (pintype "passive"))
      (node (ref "U3") (pin "5") (pinfunction "PF0-OSC_IN(PF0)_5") (pintype "bidirectional"))
      (node (ref "Y1") (pin "3") (pinfunction "OSC2_3") (pintype "passive"))
    )
    (net (code "46") (name "Net-(U3A-PF1-OSC_OUT(PF1))") (class "Default")
      (node (ref "C23") (pin "2") (pinfunction "2_2") (pintype "passive"))
      (node (ref "U3") (pin "6") (pinfunction "PF1-OSC_OUT(PF1)_6") (pintype "bidirectional"))
      (node (ref "Y1") (pin "1") (pinfunction "OSC1_1") (pintype "passive"))
    )
    (net (code "47") (name "Net-(U4-REF)") (class "Default")
      (node (ref "R26") (pin "1") (pinfunction "1_1") (pintype "passive"))
      (node (ref "R27") (pin "2") (pinfunction "2_2") (pintype "passive"))
      (node (ref "U4") (pin "2") (pinfunction "REF_2") (pintype "input"))
    )
    (net (code "48") (name "Net-(U5-BST)") (class "Default")
      (node (ref "C25") (pin "2") (pinfunction "2_2") (pintype "passive"))
      (node (ref "U5") (pin "1") (pinfunction "BST_1") (pintype "passive"))
    )
    (net (code "49") (name "Net-(U5-EN)") (class "Default")
      (node (ref "R30") (pin "1") (pinfunction "1_1") (pintype "passive"))
      (node (ref "R32") (pin "2") (pinfunction "2_2") (pintype "passive"))
      (node (ref "U5") (pin "4") (pinfunction "EN_4") (pintype "passive"))
    )
    (net (code "50") (name "Net-(U5-FB)") (class "Default")
      (node (ref "R31") (pin "1") (pinfunction "1_1") (pintype "passive"))
      (node (ref "R33") (pin "2") (pinfunction "2_2") (pintype "passive"))
      (node (ref "U5") (pin "3") (pinfunction "FB_3") (pintype "passive"))
    )
    (net (code "51") (name "VBUS") (class "Default")
      (node (ref "C1") (pin "2") (pinfunction "2_2") (pintype "passive"))
      (node (ref "C26") (pin "2") (pinfunction "2_2") (pintype "passive"))
      (node (ref "C3") (pin "1") (pintype "passive"))
      (node (ref "L1") (pin "2") (pinfunction "2_2") (pintype "passive"))
      (node (ref "Q1") (pin "3") (pinfunction "S_3") (pintype "passive"))
      (node (ref "Q2") (pin "3") (pinfunction "S_3") (pintype "passive"))
      (node (ref "R1") (pin "1") (pinfunction "1_1") (pintype "passive"))
      (node (ref "R30") (pin "2") (pinfunction "2_2") (pintype "passive"))
      (node (ref "R7") (pin "1") (pinfunction "1_1") (pintype "passive"))
      (node (ref "R8") (pin "2") (pinfunction "2_2") (pintype "passive"))
      (node (ref "U5") (pin "5") (pinfunction "VIN_5") (pintype "passive"))
    )
    (net (code "52") (name "VCC") (class "Default")
      (node (ref "P3") (pin "3") (pinfunction "3_3") (pintype "passive"))
      (node (ref "P4") (pin "2") (pinfunction "2_2") (pintype "passive"))
    )
    (net (code "53") (name "VCC3V3") (class "Default")
      (node (ref "C15") (pin "2") (pinfunction "2_2") (pintype "passive"))
      (node (ref "C16") (pin "2") (pinfunction "2_2") (pintype "passive"))
      (node (ref "C17") (pin "2") (pinfunction "2_2") (pintype "passive"))
      (node (ref "C30") (pin "2") (pinfunction "2_2") (pintype "passive"))
      (node (ref "C31") (pin "2") (pinfunction "2_2") (pintype "passive"))
      (node (ref "C32") (pin "1") (pinfunction "1_1") (pintype "passive"))
      (node (ref "C33") (pin "1") (pinfunction "1_1") (pintype "passive"))
      (node (ref "P2") (pin "11") (pinfunction "11_11") (pintype "passive"))
      (node (ref "P2") (pin "12") (pinfunction "12_12") (pintype "passive"))
      (node (ref "R16") (pin "2") (pinfunction "2_2") (pintype "passive"))
      (node (ref "R29") (pin "2") (pinfunction "2_2") (pintype "passive"))
      (node (ref "R35") (pin "1") (pinfunction "1_1") (pintype "passive"))
      (node (ref "U1") (pin "8") (pinfunction "+VS_8") (pintype "passive"))
      (node (ref "U2") (pin "8") (pinfunction "+VS_8") (pintype "passive"))
      (node (ref "U3") (pin "1") (pinfunction "VBAT_1") (pintype "power_in"))
      (node (ref "U3") (pin "24") (pinfunction "VDD_2_24") (pintype "power_in"))
      (node (ref "U3") (pin "36") (pinfunction "VDD_3_36") (pintype "power_in"))
      (node (ref "U3") (pin "48") (pinfunction "VDD_1_48") (pintype "power_in"))
      (node (ref "VR1") (pin "3") (pinfunction "Vout_3") (pintype "passive"))
    )
    (net (code "54") (name "VCC5V") (class "Default")
      (node (ref "C20") (pin "2") (pinfunction "2_2") (pintype "passive"))
      (node (ref "C21") (pin "2") (pinfunction "2_2") (pintype "passive"))
      (node (ref "C27") (pin "2") (pinfunction "2_2") (pintype "passive"))
      (node (ref "C28") (pin "2") (pinfunction "2_2") (pintype "passive"))
      (node (ref "C29") (pin "2") (pinfunction "2_2") (pintype "passive"))
      (node (ref "L2") (pin "2") (pinfunction "2_2") (pintype "passive"))
      (node (ref "R25") (pin "1") (pinfunction "1_1") (pintype "passive"))
      (node (ref "R31") (pin "2") (pinfunction "2_2") (pintype "passive"))
      (node (ref "VR1") (pin "2") (pinfunction "Vin_2") (pintype "passive"))
    )
    (net (code "55") (name "unconnected-(U3A-PA8-Pad29)") (class "Default")
      (node (ref "U3") (pin "29") (pinfunction "PA8_29") (pintype "bidirectional"))
    )
    (net (code "56") (name "unconnected-(U3A-PA11-Pad32)") (class "Default")
      (node (ref "U3") (pin "32") (pinfunction "PA11_32") (pintype "bidirectional"))
    )
    (net (code "57") (name "unconnected-(U3A-PA12-Pad33)") (class "Default")
      (node (ref "U3") (pin "33") (pinfunction "PA12_33") (pintype "bidirectional"))
    )
    (net (code "58") (name "unconnected-(U3A-PA15-Pad38)") (class "Default")
      (node (ref "U3") (pin "38") (pinfunction "PA15_38") (pintype "bidirectional"))
    )
    (net (code "59") (name "unconnected-(U3A-PB3-Pad39)") (class "Default")
      (node (ref "U3") (pin "39") (pinfunction "PB3_39") (pintype "bidirectional"))
    )
    (net (code "60") (name "unconnected-(U3A-PB4-Pad40)") (class "Default")
      (node (ref "U3") (pin "40") (pinfunction "PB4_40") (pintype "bidirectional"))
    )
    (net (code "61") (name "unconnected-(U3A-PB5-Pad41)") (class "Default")
      (node (ref "U3") (pin "41") (pinfunction "PB5_41") (pintype "bidirectional"))
    )
    (net (code "62") (name "unconnected-(U3A-PB6-Pad42)") (class "Default")
      (node (ref "U3") (pin "42") (pinfunction "PB6_42") (pintype "bidirectional"))
    )
    (net (code "63") (name "unconnected-(U3A-PB7-Pad43)") (class "Default")
      (node (ref "U3") (pin "43") (pinfunction "PB7_43") (pintype "bidirectional"))
    )
    (net (code "64") (name "unconnected-(U3A-PB8-Pad45)") (class "Default")
      (node (ref "U3") (pin "45") (pinfunction "PB8_45") (pintype "bidirectional"))
    )
    (net (code "65") (name "unconnected-(U3A-PB9-Pad46)") (class "Default")
      (node (ref "U3") (pin "46") (pinfunction "PB9_46") (pintype "bidirectional"))
    )
    (net (code "66") (name "unconnected-(U3A-PB13-Pad26)") (class "Default")
      (node (ref "U3") (pin "26") (pinfunction "PB13_26") (pintype "bidirectional"))
    )
    (net (code "67") (name "unconnected-(U3A-PB14-Pad27)") (class "Default")
      (node (ref "U3") (pin "27") (pinfunction "PB14_27") (pintype "bidirectional"))
    )
    (net (code "68") (name "unconnected-(U3A-PB15-Pad28)") (class "Default")
      (node (ref "U3") (pin "28") (pinfunction "PB15_28") (pintype "bidirectional"))
    )
    (net (code "69") (name "unconnected-(U3A-PC13-Pad2)") (class "Default")
      (node (ref "U3") (pin "2") (pinfunction "PC13_2") (pintype "bidirectional"))
    )
    (net (code "70") (name "unconnected-(U3A-PC14-OSC32_IN(PC14)-Pad3)") (class "Default")
      (node (ref "U3") (pin "3") (pinfunction "PC14-OSC32_IN(PC14)_3") (pintype "bidirectional"))
    )
    (net (code "71") (name "unconnected-(U3A-PC15-OSC32_OUT(PC15)-Pad4)") (class "Default")
      (node (ref "U3") (pin "4") (pinfunction "PC15-OSC32_OUT(PC15)_4") (pintype "bidirectional"))
    )
    (net (code "72") (name "unconnected-(U6-Pad1)") (class "Default")
      (node (ref "U6") (pin "1") (pinfunction "1_1") (pintype "passive"))
    )
    (net (code "73") (name "unconnected-(U6-Pad2)") (class "Default")
      (node (ref "U6") (pin "2") (pinfunction "2_2") (pintype "passive"))
    )
  )
)
